# rcstick-f-pico2.net
KiCad netlist of a schematic drawn in EAGLE
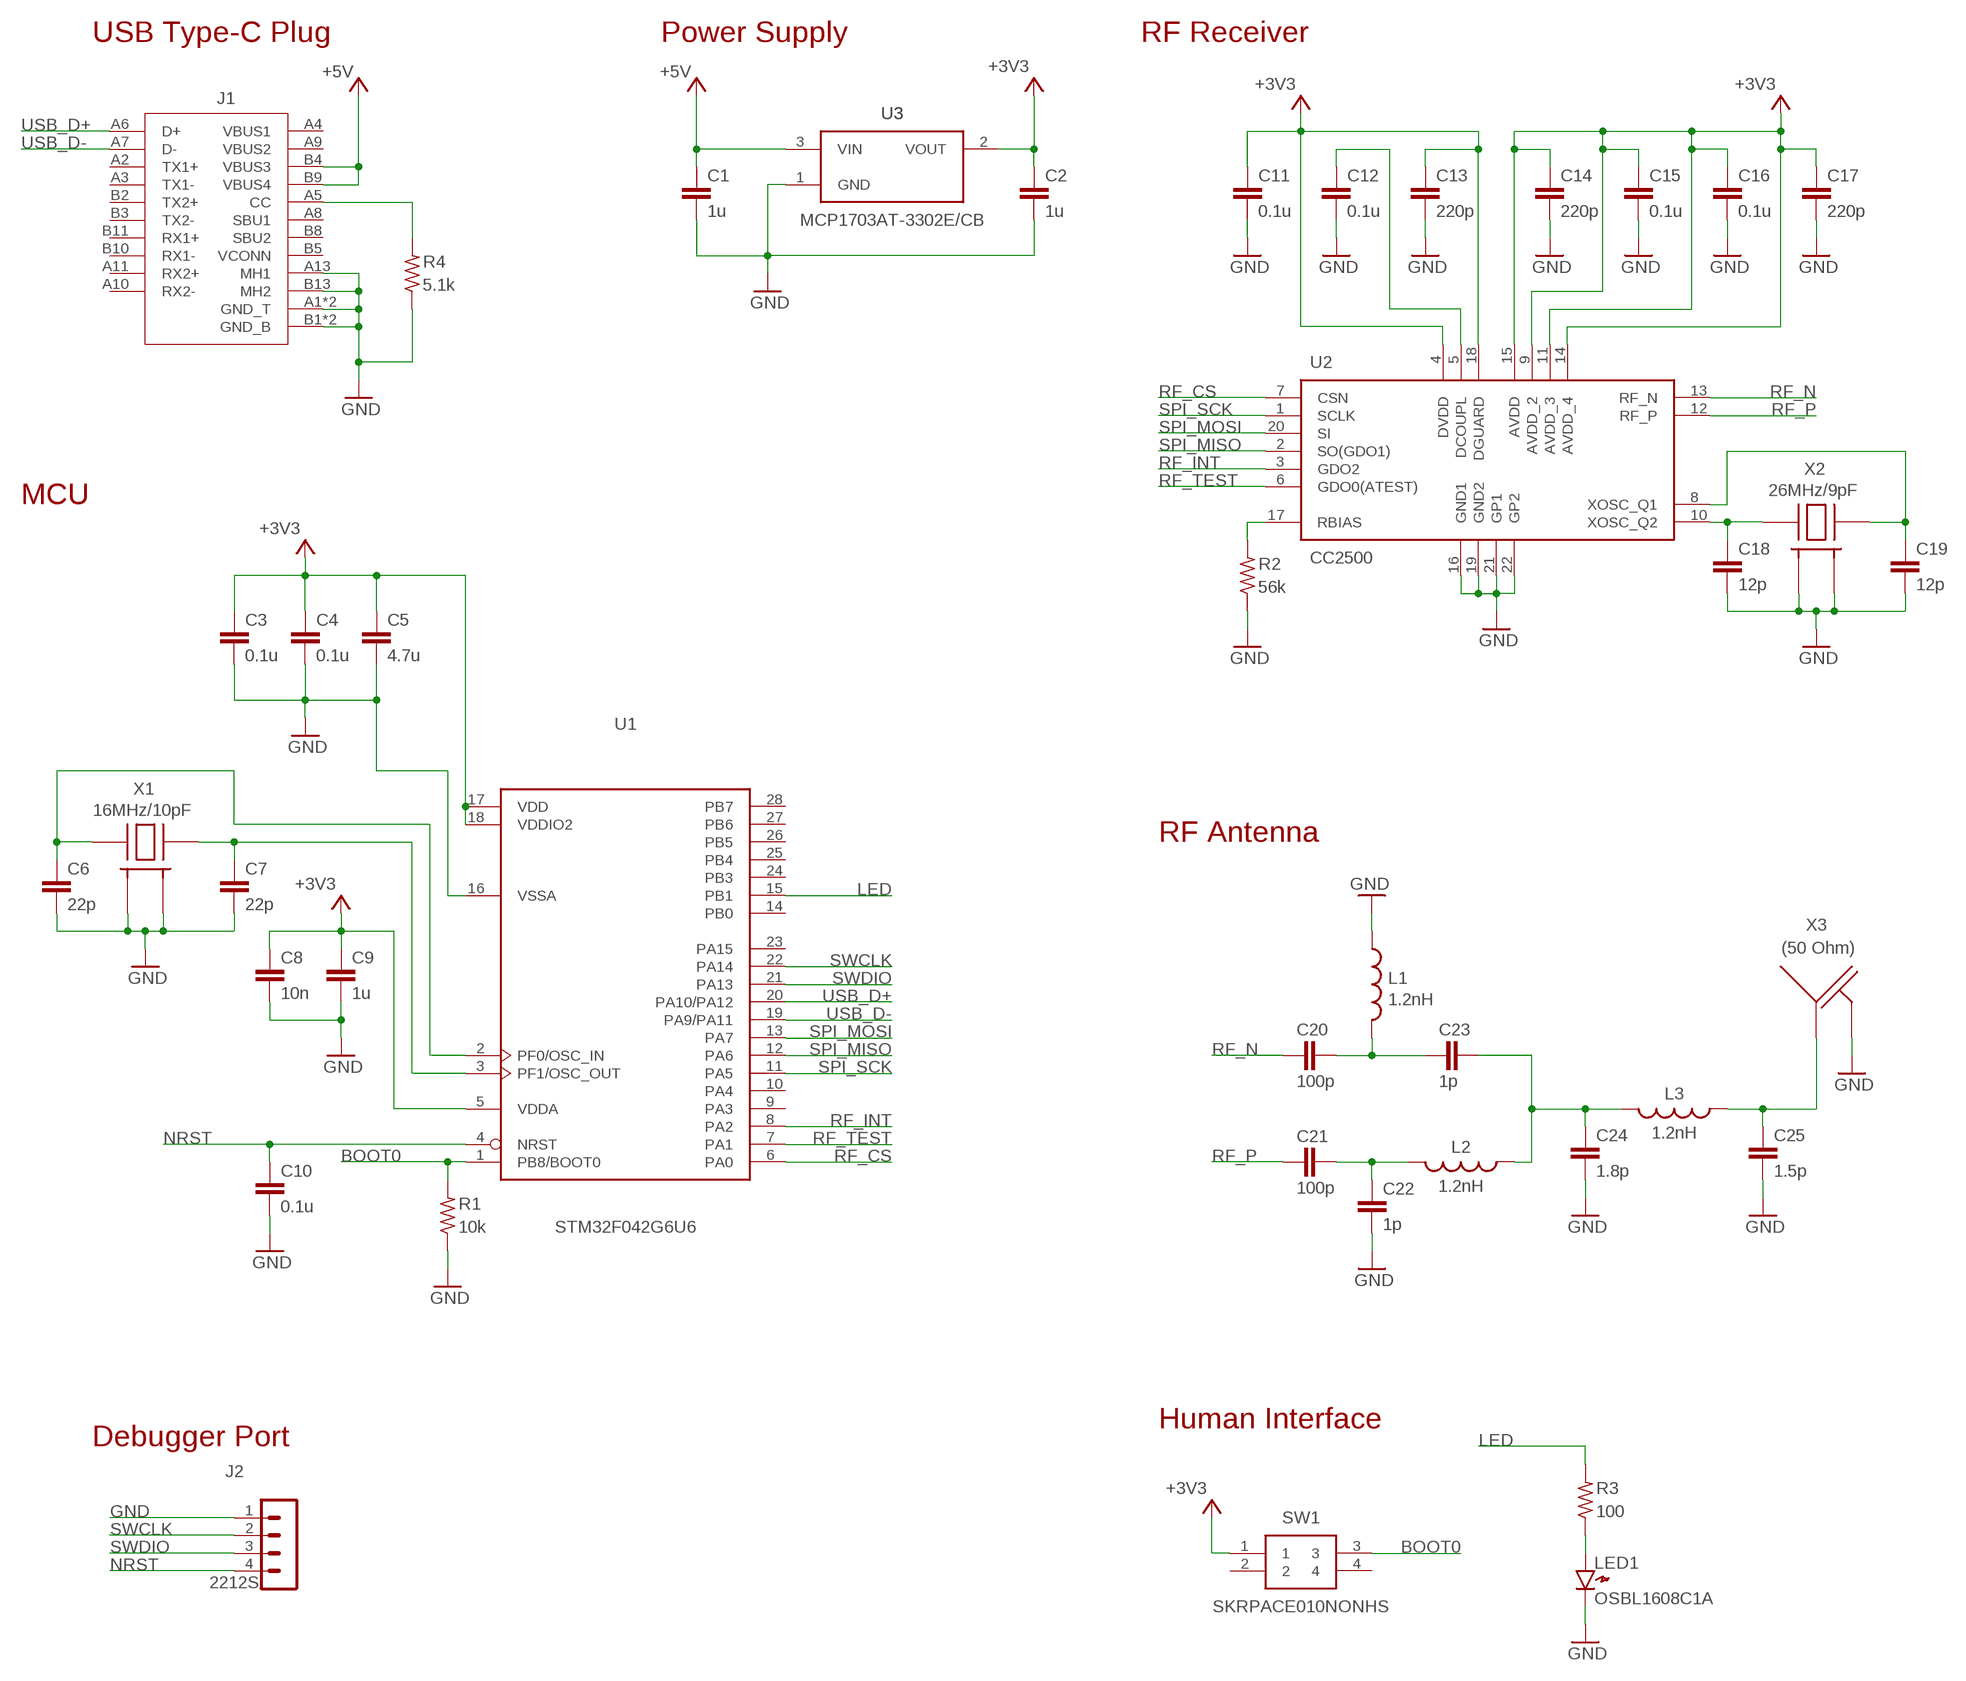
[diagram p0: schematic, sheet 1]

(export (version "E")
  (design (tool "Eeschema 10.0.6"))
  (components
    (comp (ref "C1")
      (value "1u")
      (footprint "eagle-import:RCL_C0402_HS")
      (libsource (lib "eagle-import") (part "RCL_C-EUC0402-HS"))
    )
    (comp (ref "C2")
      (value "1u")
      (footprint "eagle-import:RCL_C0402_HS")
      (libsource (lib "eagle-import") (part "RCL_C-EUC0402-HS"))
    )
    (comp (ref "C3")
      (value "0.1u")
      (footprint "eagle-import:RCL_C0402_HS")
      (libsource (lib "eagle-import") (part "RCL_C-EUC0402-HS"))
    )
    (comp (ref "C4")
      (value "0.1u")
      (footprint "eagle-import:RCL_C0402_HS")
      (libsource (lib "eagle-import") (part "RCL_C-EUC0402-HS"))
    )
    (comp (ref "C5")
      (value "4.7u")
      (footprint "eagle-import:RCL_C0402_HS")
      (libsource (lib "eagle-import") (part "RCL_C-EUC0402-HS"))
    )
    (comp (ref "C6")
      (value "22p")
      (footprint "eagle-import:RCL_C0402_HS")
      (libsource (lib "eagle-import") (part "RCL_C-EUC0402-HS"))
    )
    (comp (ref "C7")
      (value "22p")
      (footprint "eagle-import:RCL_C0402_HS")
      (libsource (lib "eagle-import") (part "RCL_C-EUC0402-HS"))
    )
    (comp (ref "C8")
      (value "10n")
      (footprint "eagle-import:RCL_C0402_HS")
      (libsource (lib "eagle-import") (part "RCL_C-EUC0402-HS"))
    )
    (comp (ref "C9")
      (value "1u")
      (footprint "eagle-import:RCL_C0402_HS")
      (libsource (lib "eagle-import") (part "RCL_C-EUC0402-HS"))
    )
    (comp (ref "C10")
      (value "0.1u")
      (footprint "eagle-import:RCL_C0402_HS")
      (libsource (lib "eagle-import") (part "RCL_C-EUC0402-HS"))
    )
    (comp (ref "C11")
      (value "0.1u")
      (footprint "eagle-import:RCL_C0402_HS")
      (libsource (lib "eagle-import") (part "RCL_C-EUC0402-HS"))
    )
    (comp (ref "C12")
      (value "0.1u")
      (footprint "eagle-import:RCL_C0402_HS")
      (libsource (lib "eagle-import") (part "RCL_C-EUC0402-HS"))
    )
    (comp (ref "C13")
      (value "220p")
      (footprint "eagle-import:RCL_C0402_HS")
      (libsource (lib "eagle-import") (part "RCL_C-EUC0402-HS"))
    )
    (comp (ref "C14")
      (value "220p")
      (footprint "eagle-import:RCL_C0402_HS")
      (libsource (lib "eagle-import") (part "RCL_C-EUC0402-HS"))
    )
    (comp (ref "C15")
      (value "0.1u")
      (footprint "eagle-import:RCL_C0402_HS")
      (libsource (lib "eagle-import") (part "RCL_C-EUC0402-HS"))
    )
    (comp (ref "C16")
      (value "0.1u")
      (footprint "eagle-import:RCL_C0402_HS")
      (libsource (lib "eagle-import") (part "RCL_C-EUC0402-HS"))
    )
    (comp (ref "C17")
      (value "220p")
      (footprint "eagle-import:RCL_C0402_HS")
      (libsource (lib "eagle-import") (part "RCL_C-EUC0402-HS"))
    )
    (comp (ref "C18")
      (value "12p")
      (footprint "eagle-import:RCL_C0402_HS")
      (libsource (lib "eagle-import") (part "RCL_C-EUC0402-HS"))
    )
    (comp (ref "C19")
      (value "12p")
      (footprint "eagle-import:RCL_C0402_HS")
      (libsource (lib "eagle-import") (part "RCL_C-EUC0402-HS"))
    )
    (comp (ref "C20")
      (value "100p")
      (footprint "eagle-import:RCL_C0402_HS")
      (libsource (lib "eagle-import") (part "RCL_C-EUC0402-HS"))
    )
    (comp (ref "C21")
      (value "100p")
      (footprint "eagle-import:RCL_C0402_HS")
      (libsource (lib "eagle-import") (part "RCL_C-EUC0402-HS"))
    )
    (comp (ref "C22")
      (value "1p")
      (footprint "eagle-import:RCL_C0402_HS")
      (libsource (lib "eagle-import") (part "RCL_C-EUC0402-HS"))
    )
    (comp (ref "C23")
      (value "1p")
      (footprint "eagle-import:RCL_C0402_HS")
      (libsource (lib "eagle-import") (part "RCL_C-EUC0402-HS"))
    )
    (comp (ref "C24")
      (value "1.8p")
      (footprint "eagle-import:RCL_C0402_HS")
      (libsource (lib "eagle-import") (part "RCL_C-EUC0402-HS"))
    )
    (comp (ref "C25")
      (value "1.5p")
      (footprint "eagle-import:RCL_C0402_HS")
      (libsource (lib "eagle-import") (part "RCL_C-EUC0402-HS"))
    )
    (comp (ref "J1")
      (value "USB-TYPEC-1054440001-HS")
      (footprint "eagle-import:USB-TYPEC-1054440001-HS")
      (libsource (lib "eagle-import") (part "USB-TYPEC-1054440001-HS"))
    )
    (comp (ref "J2")
      (value "2212S")
      (footprint "eagle-import:53047-0410")
      (libsource (lib "eagle-import") (part "53047-0410"))
    )
    (comp (ref "L1")
      (value "1.2nH")
      (footprint "eagle-import:RCL_L0402_HS")
      (libsource (lib "eagle-import") (part "RCL_L-USL0402-HS"))
    )
    (comp (ref "L2")
      (value "1.2nH")
      (footprint "eagle-import:RCL_L0402_HS")
      (libsource (lib "eagle-import") (part "RCL_L-USL0402-HS"))
    )
    (comp (ref "L3")
      (value "1.2nH")
      (footprint "eagle-import:RCL_L0402_HS")
      (libsource (lib "eagle-import") (part "RCL_L-USL0402-HS"))
    )
    (comp (ref "LED1")
      (value "OSBL1608C1A")
      (footprint "eagle-import:LED1608NONHS")
      (libsource (lib "eagle-import") (part "LED1608_NOHS"))
    )
    (comp (ref "R1")
      (value "10k")
      (footprint "eagle-import:RCL_R0402_HS")
      (libsource (lib "eagle-import") (part "RCL_R-US_R0402-HS"))
    )
    (comp (ref "R2")
      (value "56k")
      (footprint "eagle-import:RCL_R0402_HS")
      (libsource (lib "eagle-import") (part "RCL_R-US_R0402-HS"))
    )
    (comp (ref "R3")
      (value "100")
      (footprint "eagle-import:RCL_R0402_HS")
      (libsource (lib "eagle-import") (part "RCL_R-US_R0402-HS"))
    )
    (comp (ref "R4")
      (value "5.1k")
      (footprint "eagle-import:RCL_R0402_HS")
      (libsource (lib "eagle-import") (part "RCL_R-US_R0402-HS"))
    )
    (comp (ref "SW1")
      (value "SKRPACE010NONHS")
      (footprint "eagle-import:SMT(4.2X3.2)_ORG")
      (libsource (lib "eagle-import") (part "SKRPACE010NONHS"))
    )
    (comp (ref "U1")
      (value "STM32F042G6U6")
      (footprint "eagle-import:UFQFPN28")
      (libsource (lib "eagle-import") (part "STM32F042GU"))
    )
    (comp (ref "U2")
      (value "CC2500")
      (footprint "eagle-import:CC2500-RTY1_CC2500")
      (libsource (lib "eagle-import") (part "CC2500"))
    )
    (comp (ref "U3")
      (value "MCP1703AT-3302E/CB")
      (footprint "eagle-import:SOT23_NOHS")
      (libsource (lib "eagle-import") (part "LDO-REGULATOR_NOHS"))
    )
    (comp (ref "X1")
      (value "16MHz/10pF")
      (footprint "eagle-import:CRYSTAL3225")
      (libsource (lib "eagle-import") (part "CRYSTAL3225"))
    )
    (comp (ref "X2")
      (value "26MHz/9pF")
      (footprint "eagle-import:CRYSTAL3225")
      (libsource (lib "eagle-import") (part "CRYSTAL3225"))
    )
    (comp (ref "X3")
      (value "(50 Ohm)")
      (footprint "eagle-import:2.4GHZ-INVERTED-F-SMALL-FLIP")
      (libsource (lib "eagle-import") (part "2.4GHZ-INVERED-FSMALL-FLIP"))
    )
  )
  (nets
    (net (code "1") (name "+3V3") (class "Default")
      (node (ref "C11") (pin "1") (pinfunction "1_1") (pintype "passive"))
      (node (ref "C13") (pin "1") (pinfunction "1_1") (pintype "passive"))
      (node (ref "C14") (pin "1") (pinfunction "1_1") (pintype "passive"))
      (node (ref "C15") (pin "1") (pinfunction "1_1") (pintype "passive"))
      (node (ref "C16") (pin "1") (pinfunction "1_1") (pintype "passive"))
      (node (ref "C17") (pin "1") (pinfunction "1_1") (pintype "passive"))
      (node (ref "C2") (pin "1") (pinfunction "1_1") (pintype "passive"))
      (node (ref "C3") (pin "1") (pinfunction "1_1") (pintype "passive"))
      (node (ref "C4") (pin "1") (pinfunction "1_1") (pintype "passive"))
      (node (ref "C5") (pin "1") (pinfunction "1_1") (pintype "passive"))
      (node (ref "C8") (pin "1") (pinfunction "1_1") (pintype "passive"))
      (node (ref "C9") (pin "1") (pinfunction "1_1") (pintype "passive"))
      (node (ref "SW1") (pin "1") (pinfunction "1_1") (pintype "bidirectional"))
      (node (ref "U1") (pin "17") (pinfunction "VDD_17") (pintype "power_in"))
      (node (ref "U1") (pin "18") (pinfunction "VDDIO2_18") (pintype "power_in"))
      (node (ref "U1") (pin "5") (pinfunction "VDDA_5") (pintype "power_in"))
      (node (ref "U2") (pin "11") (pinfunction "AVDD_3_11") (pintype "bidirectional"))
      (node (ref "U2") (pin "14") (pinfunction "AVDD_4_14") (pintype "bidirectional"))
      (node (ref "U2") (pin "15") (pinfunction "AVDD_15") (pintype "bidirectional"))
      (node (ref "U2") (pin "18") (pinfunction "DGUARD_18") (pintype "bidirectional"))
      (node (ref "U2") (pin "4") (pinfunction "DVDD_4") (pintype "bidirectional"))
      (node (ref "U2") (pin "9") (pinfunction "AVDD_2_9") (pintype "bidirectional"))
      (node (ref "U3") (pin "2") (pinfunction "VOUT_2") (pintype "bidirectional"))
    )
    (net (code "2") (name "+5V") (class "Default")
      (node (ref "C1") (pin "1") (pinfunction "1_1") (pintype "passive"))
      (node (ref "J1") (pin "B4") (pinfunction "VBUS3_B4") (pintype "bidirectional"))
      (node (ref "J1") (pin "B9") (pinfunction "VBUS4_B9") (pintype "bidirectional"))
      (node (ref "U3") (pin "3") (pinfunction "VIN_3") (pintype "bidirectional"))
    )
    (net (code "3") (name "/BOOT0") (class "Default")
      (node (ref "R1") (pin "2") (pinfunction "2_2") (pintype "passive"))
      (node (ref "SW1") (pin "3") (pinfunction "3_3") (pintype "bidirectional"))
      (node (ref "U1") (pin "1") (pinfunction "PB8/BOOT0_1") (pintype "input"))
    )
    (net (code "4") (name "/LED") (class "Default")
      (node (ref "R3") (pin "2") (pinfunction "2_2") (pintype "passive"))
      (node (ref "U1") (pin "15") (pinfunction "PB1_15") (pintype "bidirectional"))
    )
    (net (code "5") (name "/NRST") (class "Default")
      (node (ref "C10") (pin "1") (pinfunction "1_1") (pintype "passive"))
      (node (ref "J2") (pin "4") (pinfunction "4_4") (pintype "passive"))
      (node (ref "U1") (pin "4") (pinfunction "NRST_4") (pintype "bidirectional"))
    )
    (net (code "6") (name "/RF_CS") (class "Default")
      (node (ref "U1") (pin "6") (pinfunction "PA0_6") (pintype "bidirectional"))
      (node (ref "U2") (pin "7") (pinfunction "CSN_7") (pintype "bidirectional"))
    )
    (net (code "7") (name "/RF_INT") (class "Default")
      (node (ref "U1") (pin "8") (pinfunction "PA2_8") (pintype "bidirectional"))
      (node (ref "U2") (pin "3") (pinfunction "GDO2_3") (pintype "bidirectional"))
    )
    (net (code "8") (name "/RF_N") (class "Default")
      (node (ref "C20") (pin "1") (pinfunction "1_1") (pintype "passive"))
      (node (ref "U2") (pin "13") (pinfunction "RF_N_13") (pintype "bidirectional"))
    )
    (net (code "9") (name "/RF_P") (class "Default")
      (node (ref "C21") (pin "1") (pinfunction "1_1") (pintype "passive"))
      (node (ref "U2") (pin "12") (pinfunction "RF_P_12") (pintype "bidirectional"))
    )
    (net (code "10") (name "/RF_TEST") (class "Default")
      (node (ref "U1") (pin "7") (pinfunction "PA1_7") (pintype "bidirectional"))
      (node (ref "U2") (pin "6") (pinfunction "GDO0(ATEST)_6") (pintype "bidirectional"))
    )
    (net (code "11") (name "/SPI_MISO") (class "Default")
      (node (ref "U1") (pin "12") (pinfunction "PA6_12") (pintype "bidirectional"))
      (node (ref "U2") (pin "2") (pinfunction "SO(GDO1)_2") (pintype "bidirectional"))
    )
    (net (code "12") (name "/SPI_MOSI") (class "Default")
      (node (ref "U1") (pin "13") (pinfunction "PA7_13") (pintype "bidirectional"))
      (node (ref "U2") (pin "20") (pinfunction "SI_20") (pintype "bidirectional"))
    )
    (net (code "13") (name "/SPI_SCK") (class "Default")
      (node (ref "U1") (pin "11") (pinfunction "PA5_11") (pintype "bidirectional"))
      (node (ref "U2") (pin "1") (pinfunction "SCLK_1") (pintype "bidirectional"))
    )
    (net (code "14") (name "/SWCLK") (class "Default")
      (node (ref "J2") (pin "2") (pinfunction "2_2") (pintype "passive"))
      (node (ref "U1") (pin "22") (pinfunction "PA14_22") (pintype "bidirectional"))
    )
    (net (code "15") (name "/SWDIO") (class "Default")
      (node (ref "J2") (pin "3") (pinfunction "3_3") (pintype "passive"))
      (node (ref "U1") (pin "21") (pinfunction "PA13_21") (pintype "bidirectional"))
    )
    (net (code "16") (name "/USB_D+") (class "Default")
      (node (ref "J1") (pin "A6") (pinfunction "D+_A6") (pintype "bidirectional"))
      (node (ref "U1") (pin "20") (pinfunction "PA10/PA12_20") (pintype "bidirectional"))
    )
    (net (code "17") (name "/USB_D-") (class "Default")
      (node (ref "J1") (pin "A7") (pinfunction "D-_A7") (pintype "bidirectional"))
      (node (ref "U1") (pin "19") (pinfunction "PA9/PA11_19") (pintype "bidirectional"))
    )
    (net (code "18") (name "GND") (class "Default")
      (node (ref "C1") (pin "2") (pinfunction "2_2") (pintype "passive"))
      (node (ref "C10") (pin "2") (pinfunction "2_2") (pintype "passive"))
      (node (ref "C11") (pin "2") (pinfunction "2_2") (pintype "passive"))
      (node (ref "C12") (pin "2") (pinfunction "2_2") (pintype "passive"))
      (node (ref "C13") (pin "2") (pinfunction "2_2") (pintype "passive"))
      (node (ref "C14") (pin "2") (pinfunction "2_2") (pintype "passive"))
      (node (ref "C15") (pin "2") (pinfunction "2_2") (pintype "passive"))
      (node (ref "C16") (pin "2") (pinfunction "2_2") (pintype "passive"))
      (node (ref "C17") (pin "2") (pinfunction "2_2") (pintype "passive"))
      (node (ref "C18") (pin "2") (pinfunction "2_2") (pintype "passive"))
      (node (ref "C19") (pin "2") (pinfunction "2_2") (pintype "passive"))
      (node (ref "C2") (pin "2") (pinfunction "2_2") (pintype "passive"))
      (node (ref "C22") (pin "2") (pinfunction "2_2") (pintype "passive"))
      (node (ref "C24") (pin "2") (pinfunction "2_2") (pintype "passive"))
      (node (ref "C25") (pin "2") (pinfunction "2_2") (pintype "passive"))
      (node (ref "C3") (pin "2") (pinfunction "2_2") (pintype "passive"))
      (node (ref "C4") (pin "2") (pinfunction "2_2") (pintype "passive"))
      (node (ref "C5") (pin "2") (pinfunction "2_2") (pintype "passive"))
      (node (ref "C6") (pin "2") (pinfunction "2_2") (pintype "passive"))
      (node (ref "C7") (pin "2") (pinfunction "2_2") (pintype "passive"))
      (node (ref "C8") (pin "2") (pinfunction "2_2") (pintype "passive"))
      (node (ref "C9") (pin "2") (pinfunction "2_2") (pintype "passive"))
      (node (ref "J1") (pin "A1") (pinfunction "GND_T_A1") (pintype "bidirectional"))
      (node (ref "J1") (pin "A12") (pinfunction "GND_T_A12") (pintype "bidirectional"))
      (node (ref "J1") (pin "A13") (pinfunction "MH1_A13") (pintype "bidirectional"))
      (node (ref "J1") (pin "B1") (pinfunction "GND_B_B1") (pintype "bidirectional"))
      (node (ref "J1") (pin "B12") (pinfunction "GND_B_B12") (pintype "bidirectional"))
      (node (ref "J1") (pin "B13") (pinfunction "MH2_B13") (pintype "bidirectional"))
      (node (ref "J2") (pin "1") (pinfunction "1_1") (pintype "passive"))
      (node (ref "L1") (pin "1") (pinfunction "1_1") (pintype "passive"))
      (node (ref "LED1") (pin "K") (pinfunction "K_K") (pintype "passive"))
      (node (ref "R1") (pin "1") (pinfunction "1_1") (pintype "passive"))
      (node (ref "R2") (pin "1") (pinfunction "1_1") (pintype "passive"))
      (node (ref "R4") (pin "1") (pinfunction "1_1") (pintype "passive"))
      (node (ref "U1") (pin "16") (pinfunction "VSSA_16") (pintype "power_in"))
      (node (ref "U2") (pin "16") (pinfunction "GND1_16") (pintype "bidirectional"))
      (node (ref "U2") (pin "19") (pinfunction "GND2_19") (pintype "bidirectional"))
      (node (ref "U2") (pin "21") (pinfunction "GP1_21") (pintype "bidirectional"))
      (node (ref "U2") (pin "22") (pinfunction "GP2_22") (pintype "bidirectional"))
      (node (ref "U3") (pin "1") (pinfunction "GND_1") (pintype "bidirectional"))
      (node (ref "X1") (pin "2") (pinfunction "GND_1_2") (pintype "bidirectional"))
      (node (ref "X1") (pin "4") (pinfunction "GND_2_4") (pintype "bidirectional"))
      (node (ref "X2") (pin "2") (pinfunction "GND_1_2") (pintype "bidirectional"))
      (node (ref "X2") (pin "4") (pinfunction "GND_2_4") (pintype "bidirectional"))
      (node (ref "X3") (pin "2") (pinfunction "GND_2") (pintype "bidirectional"))
    )
    (net (code "19") (name "Net-(C20-Pad2)") (class "Default")
      (node (ref "C20") (pin "2") (pinfunction "2_2") (pintype "passive"))
      (node (ref "C23") (pin "1") (pinfunction "1_1") (pintype "passive"))
      (node (ref "L1") (pin "2") (pinfunction "2_2") (pintype "passive"))
    )
    (net (code "20") (name "Net-(C21-Pad2)") (class "Default")
      (node (ref "C21") (pin "2") (pinfunction "2_2") (pintype "passive"))
      (node (ref "C22") (pin "1") (pinfunction "1_1") (pintype "passive"))
      (node (ref "L2") (pin "2") (pinfunction "2_2") (pintype "passive"))
    )
    (net (code "21") (name "Net-(C23-Pad2)") (class "Default")
      (node (ref "C23") (pin "2") (pinfunction "2_2") (pintype "passive"))
      (node (ref "C24") (pin "1") (pinfunction "1_1") (pintype "passive"))
      (node (ref "L2") (pin "1") (pinfunction "1_1") (pintype "passive"))
      (node (ref "L3") (pin "2") (pinfunction "2_2") (pintype "passive"))
    )
    (net (code "22") (name "Net-(J1-CC)") (class "Default")
      (node (ref "J1") (pin "A5") (pinfunction "CC_A5") (pintype "bidirectional"))
      (node (ref "R4") (pin "2") (pinfunction "2_2") (pintype "passive"))
    )
    (net (code "23") (name "Net-(LED1-PadA)") (class "Default")
      (node (ref "LED1") (pin "A") (pinfunction "A_A") (pintype "passive"))
      (node (ref "R3") (pin "1") (pinfunction "1_1") (pintype "passive"))
    )
    (net (code "24") (name "Net-(U1-PF0{slash}OSC_IN)") (class "Default")
      (node (ref "C6") (pin "1") (pinfunction "1_1") (pintype "passive"))
      (node (ref "U1") (pin "2") (pinfunction "PF0/OSC_IN_2") (pintype "bidirectional"))
      (node (ref "X1") (pin "1") (pinfunction "HOT_1_1") (pintype "bidirectional"))
    )
    (net (code "25") (name "Net-(U1-PF1{slash}OSC_OUT)") (class "Default")
      (node (ref "C7") (pin "1") (pinfunction "1_1") (pintype "passive"))
      (node (ref "U1") (pin "3") (pinfunction "PF1/OSC_OUT_3") (pintype "bidirectional"))
      (node (ref "X1") (pin "3") (pinfunction "HOT_2_3") (pintype "bidirectional"))
    )
    (net (code "26") (name "Net-(U2-DCOUPL)") (class "Default")
      (node (ref "C12") (pin "1") (pinfunction "1_1") (pintype "passive"))
      (node (ref "U2") (pin "5") (pinfunction "DCOUPL_5") (pintype "bidirectional"))
    )
    (net (code "27") (name "Net-(U2-RBIAS)") (class "Default")
      (node (ref "R2") (pin "2") (pinfunction "2_2") (pintype "passive"))
      (node (ref "U2") (pin "17") (pinfunction "RBIAS_17") (pintype "bidirectional"))
    )
    (net (code "28") (name "Net-(U2-XOSC_Q1)") (class "Default")
      (node (ref "C19") (pin "1") (pinfunction "1_1") (pintype "passive"))
      (node (ref "U2") (pin "8") (pinfunction "XOSC_Q1_8") (pintype "bidirectional"))
      (node (ref "X2") (pin "3") (pinfunction "HOT_2_3") (pintype "bidirectional"))
    )
    (net (code "29") (name "Net-(U2-XOSC_Q2)") (class "Default")
      (node (ref "C18") (pin "1") (pinfunction "1_1") (pintype "passive"))
      (node (ref "U2") (pin "10") (pinfunction "XOSC_Q2_10") (pintype "bidirectional"))
      (node (ref "X2") (pin "1") (pinfunction "HOT_1_1") (pintype "bidirectional"))
    )
    (net (code "30") (name "Net-(X3-ANT)") (class "Default")
      (node (ref "C25") (pin "1") (pinfunction "1_1") (pintype "passive"))
      (node (ref "L3") (pin "1") (pinfunction "1_1") (pintype "passive"))
      (node (ref "X3") (pin "1") (pinfunction "ANT_1") (pintype "bidirectional"))
    )
    (net (code "31") (name "unconnected-(J1-RX1+-PadB11)") (class "Default")
      (node (ref "J1") (pin "B11") (pinfunction "RX1+_B11") (pintype "bidirectional"))
    )
    (net (code "32") (name "unconnected-(J1-RX1--PadB10)") (class "Default")
      (node (ref "J1") (pin "B10") (pinfunction "RX1-_B10") (pintype "bidirectional"))
    )
    (net (code "33") (name "unconnected-(J1-RX2+-PadA11)") (class "Default")
      (node (ref "J1") (pin "A11") (pinfunction "RX2+_A11") (pintype "bidirectional"))
    )
    (net (code "34") (name "unconnected-(J1-RX2--PadA10)") (class "Default")
      (node (ref "J1") (pin "A10") (pinfunction "RX2-_A10") (pintype "bidirectional"))
    )
    (net (code "35") (name "unconnected-(J1-SBU1-PadA8)") (class "Default")
      (node (ref "J1") (pin "A8") (pinfunction "SBU1_A8") (pintype "bidirectional"))
    )
    (net (code "36") (name "unconnected-(J1-SBU2-PadB8)") (class "Default")
      (node (ref "J1") (pin "B8") (pinfunction "SBU2_B8") (pintype "bidirectional"))
    )
    (net (code "37") (name "unconnected-(J1-TX1+-PadA2)") (class "Default")
      (node (ref "J1") (pin "A2") (pinfunction "TX1+_A2") (pintype "bidirectional"))
    )
    (net (code "38") (name "unconnected-(J1-TX1--PadA3)") (class "Default")
      (node (ref "J1") (pin "A3") (pinfunction "TX1-_A3") (pintype "bidirectional"))
    )
    (net (code "39") (name "unconnected-(J1-TX2+-PadB2)") (class "Default")
      (node (ref "J1") (pin "B2") (pinfunction "TX2+_B2") (pintype "bidirectional"))
    )
    (net (code "40") (name "unconnected-(J1-TX2--PadB3)") (class "Default")
      (node (ref "J1") (pin "B3") (pinfunction "TX2-_B3") (pintype "bidirectional"))
    )
    (net (code "41") (name "unconnected-(J1-VBUS1-PadA4)") (class "Default")
      (node (ref "J1") (pin "A4") (pinfunction "VBUS1_A4") (pintype "bidirectional"))
    )
    (net (code "42") (name "unconnected-(J1-VBUS2-PadA9)") (class "Default")
      (node (ref "J1") (pin "A9") (pinfunction "VBUS2_A9") (pintype "bidirectional"))
    )
    (net (code "43") (name "unconnected-(J1-VCONN-PadB5)") (class "Default")
      (node (ref "J1") (pin "B5") (pinfunction "VCONN_B5") (pintype "bidirectional"))
    )
    (net (code "44") (name "unconnected-(SW1-Pad2)") (class "Default")
      (node (ref "SW1") (pin "2") (pinfunction "2_2") (pintype "bidirectional"))
    )
    (net (code "45") (name "unconnected-(SW1-Pad4)") (class "Default")
      (node (ref "SW1") (pin "4") (pinfunction "4_4") (pintype "bidirectional"))
    )
    (net (code "46") (name "unconnected-(U1-PA3-Pad9)") (class "Default")
      (node (ref "U1") (pin "9") (pinfunction "PA3_9") (pintype "bidirectional"))
    )
    (net (code "47") (name "unconnected-(U1-PA4-Pad10)") (class "Default")
      (node (ref "U1") (pin "10") (pinfunction "PA4_10") (pintype "bidirectional"))
    )
    (net (code "48") (name "unconnected-(U1-PA15-Pad23)") (class "Default")
      (node (ref "U1") (pin "23") (pinfunction "PA15_23") (pintype "bidirectional"))
    )
    (net (code "49") (name "unconnected-(U1-PB0-Pad14)") (class "Default")
      (node (ref "U1") (pin "14") (pinfunction "PB0_14") (pintype "bidirectional"))
    )
    (net (code "50") (name "unconnected-(U1-PB3-Pad24)") (class "Default")
      (node (ref "U1") (pin "24") (pinfunction "PB3_24") (pintype "bidirectional"))
    )
    (net (code "51") (name "unconnected-(U1-PB4-Pad25)") (class "Default")
      (node (ref "U1") (pin "25") (pinfunction "PB4_25") (pintype "bidirectional"))
    )
    (net (code "52") (name "unconnected-(U1-PB5-Pad26)") (class "Default")
      (node (ref "U1") (pin "26") (pinfunction "PB5_26") (pintype "bidirectional"))
    )
    (net (code "53") (name "unconnected-(U1-PB6-Pad27)") (class "Default")
      (node (ref "U1") (pin "27") (pinfunction "PB6_27") (pintype "bidirectional"))
    )
    (net (code "54") (name "unconnected-(U1-PB7-Pad28)") (class "Default")
      (node (ref "U1") (pin "28") (pinfunction "PB7_28") (pintype "bidirectional"))
    )
  )
)
